# SD.net
KiCad netlist of a schematic drawn in Altium Designer
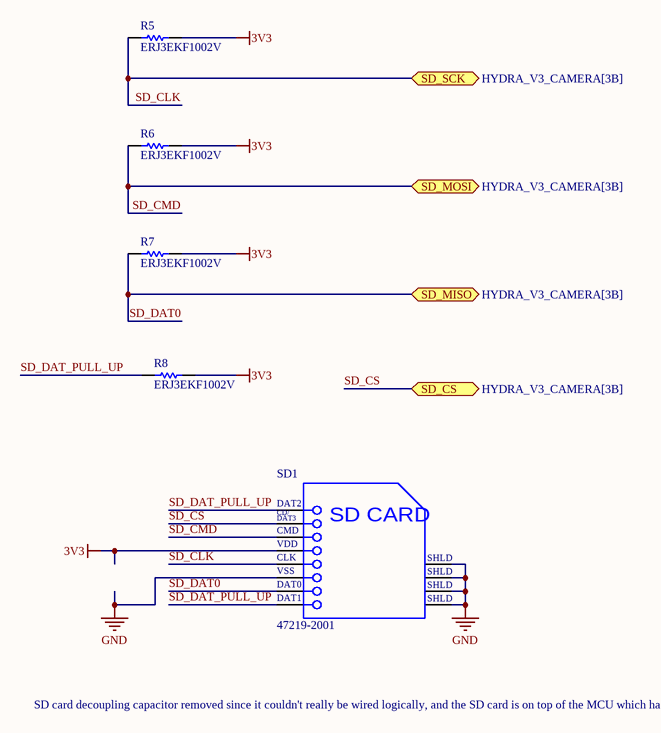
[diagram p0: SD.SchDoc]

(export (version "E")
  (design (tool "Eeschema 10.0.6"))
  (components
    (comp (ref "R5")
      (value "ERJ3EKF1002V")
      (footprint "RESC1609X55X30LL15T15")
      (description "Chip Resistor, 10 KOhm, +/- 1%, 0.1 W, -55 to 155 degC, 0603 (1608 Metric), RoHS, Tape and Reel")
      (fields (field (name "TOLERANCE") "1%") (field (name "MANUFACTURER") "Panasonic"))
      (libsource (lib "Altium Content Vault") (part "RES-2"))
    )
    (comp (ref "R6")
      (value "ERJ3EKF1002V")
      (footprint "RESC1609X55X30LL15T15")
      (description "Chip Resistor, 10 KOhm, +/- 1%, 0.1 W, -55 to 155 degC, 0603 (1608 Metric), RoHS, Tape and Reel")
      (fields (field (name "TOLERANCE") "1%") (field (name "MANUFACTURER") "Panasonic"))
      (libsource (lib "Altium Content Vault") (part "RES-2"))
    )
    (comp (ref "R7")
      (value "ERJ3EKF1002V")
      (footprint "RESC1609X55X30LL15T15")
      (description "Chip Resistor, 10 KOhm, +/- 1%, 0.1 W, -55 to 155 degC, 0603 (1608 Metric), RoHS, Tape and Reel")
      (fields (field (name "TOLERANCE") "1%") (field (name "MANUFACTURER") "Panasonic"))
      (libsource (lib "Altium Content Vault") (part "RES-2"))
    )
    (comp (ref "R8")
      (value "ERJ3EKF1002V")
      (footprint "RESC1609X55X30LL15T15")
      (description "Chip Resistor, 10 KOhm, +/- 1%, 0.1 W, -55 to 155 degC, 0603 (1608 Metric), RoHS, Tape and Reel")
      (fields (field (name "TOLERANCE") "1%") (field (name "MANUFACTURER") "Panasonic"))
      (libsource (lib "Altium Content Vault") (part "RES-2"))
    )
    (comp (ref "SD1")
      (value "47219-2001")
      (footprint "MOLX-47219-2001-8_V")
      (description "MicroSD Card Connector, Hinge Type, -40 to 85 degC, 8-Pin SMD, RoHS, Tape and Reel")
      (fields (field (name "MANUFACTURER") "Molex"))
      (libsource (lib "Altium Content Vault") (part "CN-SD-8-4S"))
    )
  )
  (nets
    (net (code "1") (name "/SD_CLK") (class "Default")
      (node (ref "R5") (pin "1") (pinfunction "1_1") (pintype "passive"))
      (node (ref "SD1") (pin "5") (pinfunction "CLK_5") (pintype "passive"))
    )
    (net (code "2") (name "/SD_CMD") (class "Default")
      (node (ref "R6") (pin "1") (pinfunction "1_1") (pintype "passive"))
      (node (ref "SD1") (pin "3") (pinfunction "CMD_3") (pintype "passive"))
    )
    (net (code "3") (name "/SD_CS") (class "Default")
      (node (ref "SD1") (pin "2") (pinfunction "CD/DAT3_2") (pintype "passive"))
    )
    (net (code "4") (name "/SD_DAT0") (class "Default")
      (node (ref "R7") (pin "1") (pinfunction "1_1") (pintype "passive"))
      (node (ref "SD1") (pin "7") (pinfunction "DAT0_7") (pintype "passive"))
    )
    (net (code "5") (name "/SD_DAT_PULL_UP") (class "Default")
      (node (ref "R8") (pin "1") (pinfunction "1_1") (pintype "passive"))
      (node (ref "SD1") (pin "1") (pinfunction "DAT2_1") (pintype "passive"))
      (node (ref "SD1") (pin "8") (pinfunction "DAT1_8") (pintype "passive"))
    )
    (net (code "6") (name "3V3") (class "Default")
      (node (ref "R5") (pin "2") (pinfunction "2_2") (pintype "passive"))
      (node (ref "R6") (pin "2") (pinfunction "2_2") (pintype "passive"))
      (node (ref "R7") (pin "2") (pinfunction "2_2") (pintype "passive"))
      (node (ref "R8") (pin "2") (pinfunction "2_2") (pintype "passive"))
      (node (ref "SD1") (pin "4") (pinfunction "VDD_4") (pintype "passive"))
    )
    (net (code "7") (name "GND") (class "Default")
      (node (ref "SD1") (pin "10") (pinfunction "SHLD_10") (pintype "passive"))
      (node (ref "SD1") (pin "11") (pinfunction "SHLD_11") (pintype "passive"))
      (node (ref "SD1") (pin "12") (pinfunction "SHLD_12") (pintype "passive"))
      (node (ref "SD1") (pin "6") (pinfunction "VSS_6") (pintype "passive"))
      (node (ref "SD1") (pin "9") (pinfunction "SHLD_9") (pintype "passive"))
    )
  )
)
